# 05_Miniport_Host.net
KiCad netlist of a schematic drawn in Altium Designer
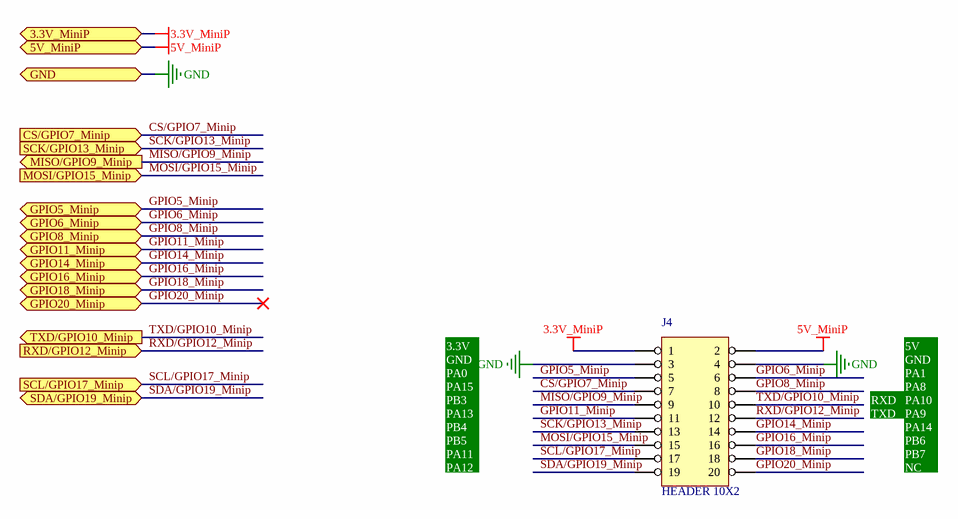
[diagram p0: 05.Miniport_Host.SchDoc]

(export (version "E")
  (design (tool "Eeschema 10.0.6"))
  (components
    (comp (ref "J4")
      (value "HEADER 10X2")
      (footprint "无需物料号元件:IDC-20-2.54-R90")
      (libsource (lib "无需物料号元件") (part "HEADER 10X2"))
    )
  )
  (nets
    (net (code "1") (name "/CS{slash}GPIO7_Minip") (class "Default")
      (node (ref "J4") (pin "7") (pinfunction "7_7") (pintype "passive"))
    )
    (net (code "2") (name "/GPIO5_Minip") (class "Default")
      (node (ref "J4") (pin "5") (pinfunction "5_5") (pintype "passive"))
    )
    (net (code "3") (name "/GPIO6_Minip") (class "Default")
      (node (ref "J4") (pin "6") (pinfunction "6_6") (pintype "passive"))
    )
    (net (code "4") (name "/GPIO8_Minip") (class "Default")
      (node (ref "J4") (pin "8") (pinfunction "8_8") (pintype "passive"))
    )
    (net (code "5") (name "/GPIO11_Minip") (class "Default")
      (node (ref "J4") (pin "11") (pinfunction "11_11") (pintype "passive"))
    )
    (net (code "6") (name "/GPIO14_Minip") (class "Default")
      (node (ref "J4") (pin "14") (pinfunction "14_14") (pintype "passive"))
    )
    (net (code "7") (name "/GPIO16_Minip") (class "Default")
      (node (ref "J4") (pin "16") (pinfunction "16_16") (pintype "passive"))
    )
    (net (code "8") (name "/GPIO18_Minip") (class "Default")
      (node (ref "J4") (pin "18") (pinfunction "18_18") (pintype "passive"))
    )
    (net (code "9") (name "/GPIO20_Minip") (class "Default")
      (node (ref "J4") (pin "20") (pinfunction "20_20") (pintype "passive"))
    )
    (net (code "10") (name "/MISO{slash}GPIO9_Minip") (class "Default")
      (node (ref "J4") (pin "9") (pinfunction "9_9") (pintype "passive"))
    )
    (net (code "11") (name "/MOSI{slash}GPIO15_Minip") (class "Default")
      (node (ref "J4") (pin "15") (pinfunction "15_15") (pintype "passive"))
    )
    (net (code "12") (name "/RXD{slash}GPIO12_Minip") (class "Default")
      (node (ref "J4") (pin "12") (pinfunction "12_12") (pintype "passive"))
    )
    (net (code "13") (name "/SCK{slash}GPIO13_Minip") (class "Default")
      (node (ref "J4") (pin "13") (pinfunction "13_13") (pintype "passive"))
    )
    (net (code "14") (name "/SCL{slash}GPIO17_Minip") (class "Default")
      (node (ref "J4") (pin "17") (pinfunction "17_17") (pintype "passive"))
    )
    (net (code "15") (name "/SDA{slash}GPIO19_Minip") (class "Default")
      (node (ref "J4") (pin "19") (pinfunction "19_19") (pintype "passive"))
    )
    (net (code "16") (name "/TXD{slash}GPIO10_Minip") (class "Default")
      (node (ref "J4") (pin "10") (pinfunction "10_10") (pintype "passive"))
    )
    (net (code "17") (name "3.3V_MiniP") (class "Default")
      (node (ref "J4") (pin "1") (pinfunction "1_1") (pintype "passive"))
    )
    (net (code "18") (name "5V_MiniP") (class "Default")
      (node (ref "J4") (pin "2") (pinfunction "2_2") (pintype "passive"))
    )
    (net (code "19") (name "GND") (class "Default")
      (node (ref "J4") (pin "3") (pinfunction "3_3") (pintype "passive"))
      (node (ref "J4") (pin "4") (pinfunction "4_4") (pintype "passive"))
    )
  )
)
